# 9xVoice_MikeB_SMD_v101.net
KiCad netlist of a schematic drawn in EAGLE
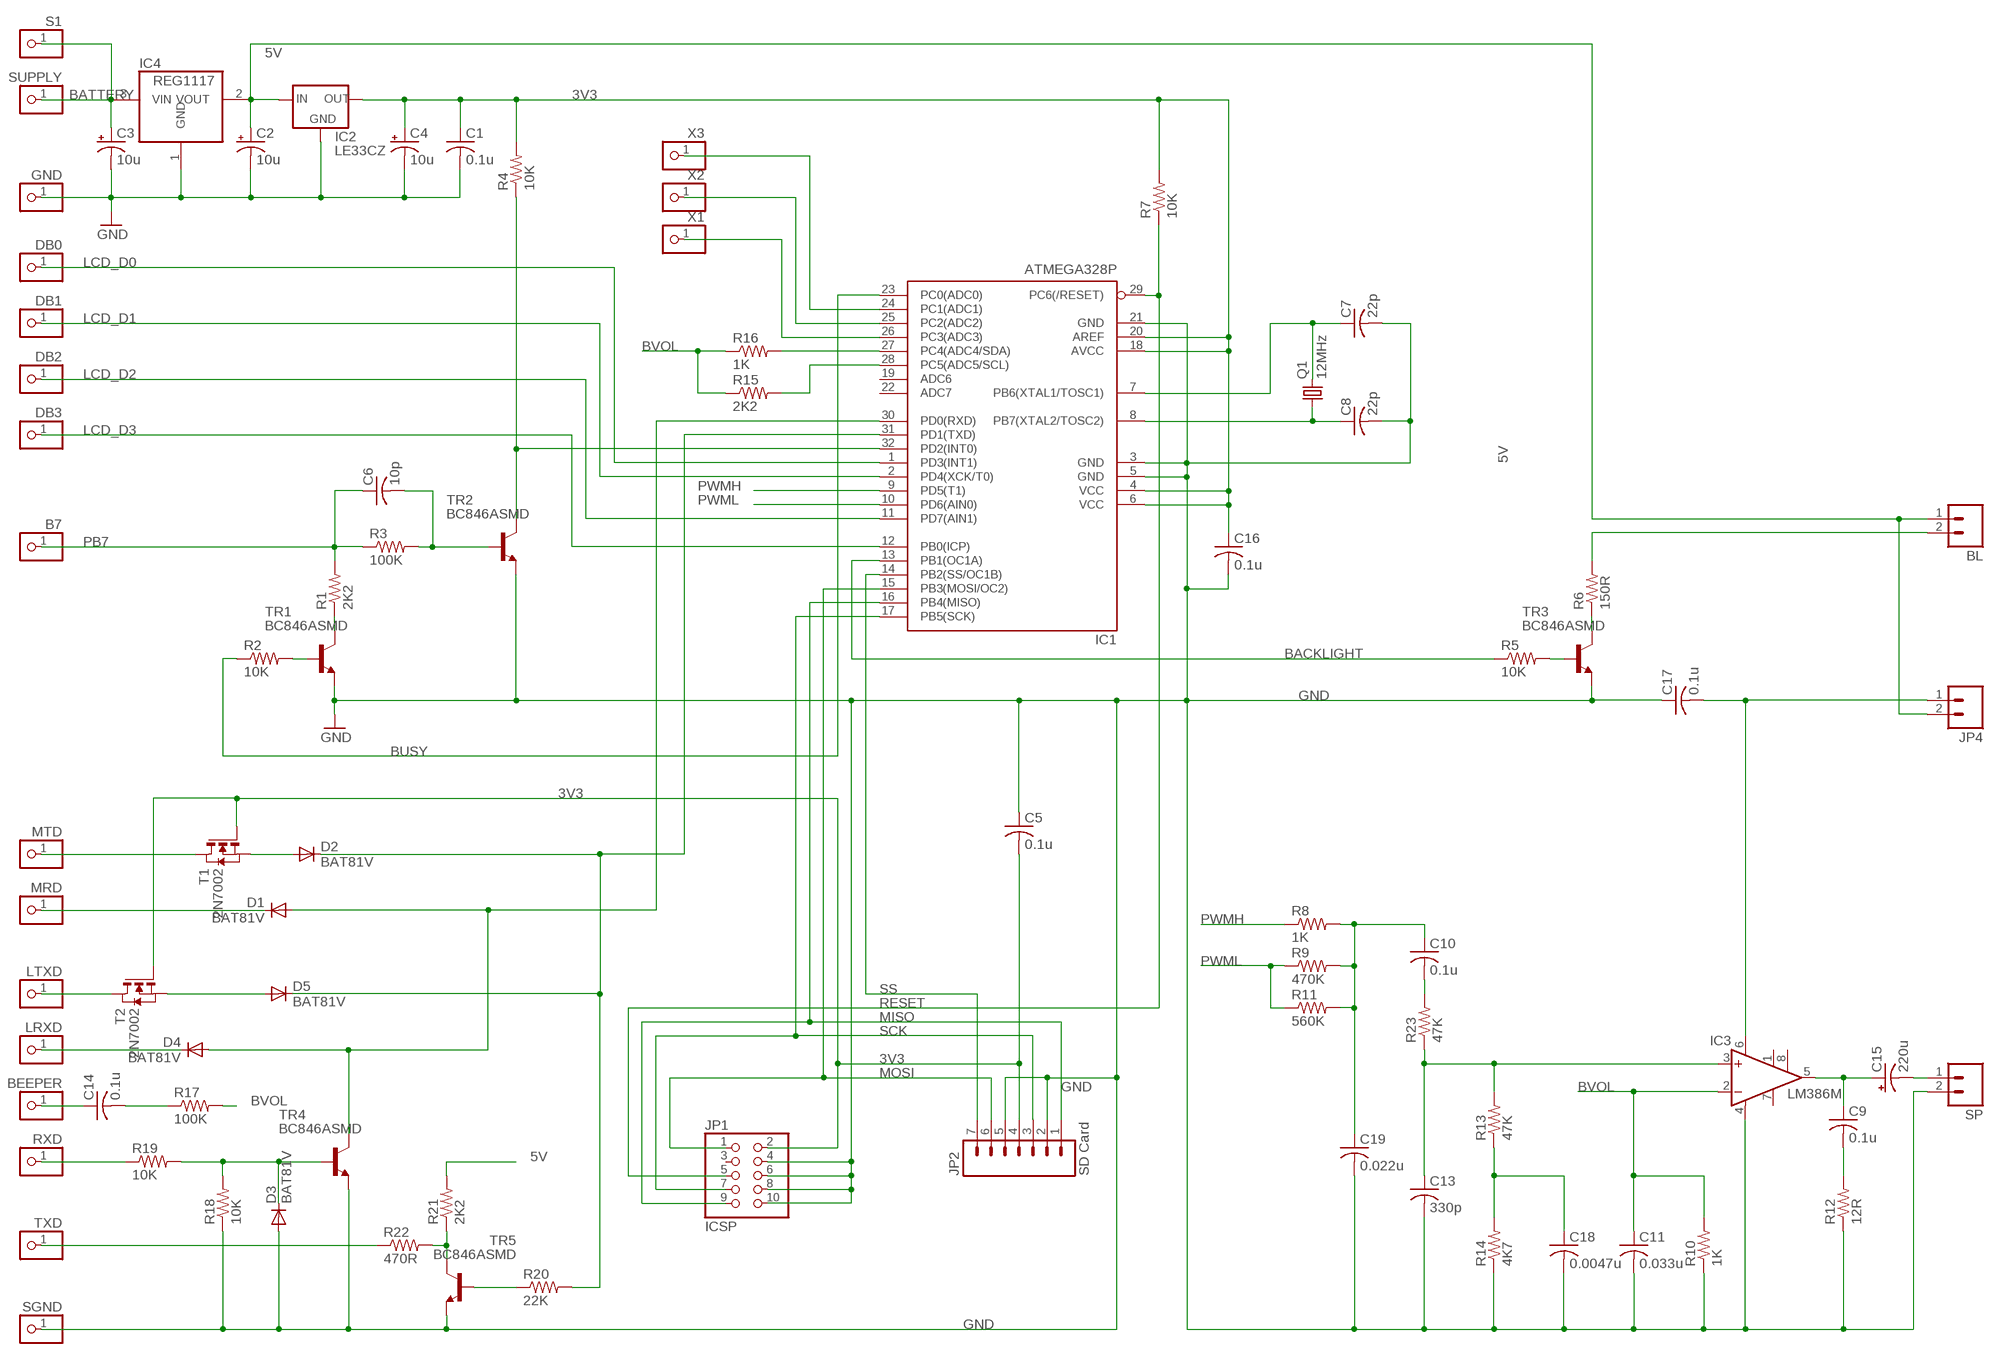
[diagram p0: schematic, sheet 1]

(export (version "E")
  (design (tool "Eeschema 10.0.6"))
  (components
    (comp (ref "B7")
      (value "PINHD-1X1")
      (footprint "eagle-import:1X01")
      (libsource (lib "eagle-import") (part "PINHD-1X1"))
    )
    (comp (ref "BEEPER")
      (value "PINHD-1X1")
      (footprint "eagle-import:1X01")
      (libsource (lib "eagle-import") (part "PINHD-1X1"))
    )
    (comp (ref "BL")
      (value "M02PTH")
      (footprint "eagle-import:1X02")
      (libsource (lib "eagle-import") (part "M02PTH"))
    )
    (comp (ref "C1")
      (value "0.1u")
      (footprint "eagle-import:C1206")
      (libsource (lib "eagle-import") (part "C-USC1206"))
    )
    (comp (ref "C2")
      (value "10u")
      (footprint "eagle-import:A_3216-18R")
      (libsource (lib "eagle-import") (part "CPOL-USA/3216-18R"))
    )
    (comp (ref "C3")
      (value "10u")
      (footprint "eagle-import:A_3216-18R")
      (libsource (lib "eagle-import") (part "CPOL-USA/3216-18R"))
    )
    (comp (ref "C4")
      (value "10u")
      (footprint "eagle-import:A_3216-18R")
      (libsource (lib "eagle-import") (part "CPOL-USA/3216-18R"))
    )
    (comp (ref "C5")
      (value "0.1u")
      (footprint "eagle-import:C1206")
      (libsource (lib "eagle-import") (part "C-USC1206"))
    )
    (comp (ref "C6")
      (value "10p")
      (footprint "eagle-import:C1206")
      (libsource (lib "eagle-import") (part "C-USC1206"))
    )
    (comp (ref "C7")
      (value "22p")
      (footprint "eagle-import:C1206")
      (libsource (lib "eagle-import") (part "C-USC1206"))
    )
    (comp (ref "C8")
      (value "22p")
      (footprint "eagle-import:C1206")
      (libsource (lib "eagle-import") (part "C-USC1206"))
    )
    (comp (ref "C9")
      (value "0.1u")
      (footprint "eagle-import:C1206")
      (libsource (lib "eagle-import") (part "C-USC1206"))
    )
    (comp (ref "C10")
      (value "0.1u")
      (footprint "eagle-import:C1206")
      (libsource (lib "eagle-import") (part "C-USC1206"))
    )
    (comp (ref "C11")
      (value "0.033u")
      (footprint "eagle-import:C1206")
      (libsource (lib "eagle-import") (part "C-USC1206"))
    )
    (comp (ref "C13")
      (value "330p")
      (footprint "eagle-import:C1206")
      (libsource (lib "eagle-import") (part "C-USC1206"))
    )
    (comp (ref "C14")
      (value "0.1u")
      (footprint "eagle-import:C1206")
      (libsource (lib "eagle-import") (part "C-USC1206"))
    )
    (comp (ref "C15")
      (value "220u")
      (footprint "eagle-import:CT7343")
      (libsource (lib "eagle-import") (part "CPOL-USCT7343"))
    )
    (comp (ref "C16")
      (value "0.1u")
      (footprint "eagle-import:C1206")
      (libsource (lib "eagle-import") (part "C-USC1206"))
    )
    (comp (ref "C17")
      (value "0.1u")
      (footprint "eagle-import:C1206")
      (libsource (lib "eagle-import") (part "C-USC1206"))
    )
    (comp (ref "C18")
      (value "0.0047u")
      (footprint "eagle-import:C1206")
      (libsource (lib "eagle-import") (part "C-USC1206"))
    )
    (comp (ref "C19")
      (value "0.022u")
      (footprint "eagle-import:C1206")
      (libsource (lib "eagle-import") (part "C-USC1206"))
    )
    (comp (ref "D1")
      (value "BAT81V")
      (footprint "eagle-import:SOD123")
      (libsource (lib "eagle-import") (part "DIODE-SOD123"))
    )
    (comp (ref "D2")
      (value "BAT81V")
      (footprint "eagle-import:SOD123")
      (libsource (lib "eagle-import") (part "DIODE-SOD123"))
    )
    (comp (ref "D3")
      (value "BAT81V")
      (footprint "eagle-import:SOD123")
      (libsource (lib "eagle-import") (part "DIODE-SOD123"))
    )
    (comp (ref "D4")
      (value "BAT81V")
      (footprint "eagle-import:SOD123")
      (libsource (lib "eagle-import") (part "DIODE-SOD123"))
    )
    (comp (ref "D5")
      (value "BAT81V")
      (footprint "eagle-import:SOD123")
      (libsource (lib "eagle-import") (part "DIODE-SOD123"))
    )
    (comp (ref "DB0")
      (value "PINHD-1X1")
      (footprint "eagle-import:1X01")
      (libsource (lib "eagle-import") (part "PINHD-1X1"))
    )
    (comp (ref "DB1")
      (value "PINHD-1X1")
      (footprint "eagle-import:1X01")
      (libsource (lib "eagle-import") (part "PINHD-1X1"))
    )
    (comp (ref "DB2")
      (value "PINHD-1X1")
      (footprint "eagle-import:1X01")
      (libsource (lib "eagle-import") (part "PINHD-1X1"))
    )
    (comp (ref "DB3")
      (value "PINHD-1X1")
      (footprint "eagle-import:1X01")
      (libsource (lib "eagle-import") (part "PINHD-1X1"))
    )
    (comp (ref "GND")
      (value "PINHD-1X1")
      (footprint "eagle-import:1X01")
      (libsource (lib "eagle-import") (part "PINHD-1X1"))
    )
    (comp (ref "IC1")
      (value "ATMEGA328P")
      (footprint "eagle-import:TQFP32-08")
      (fields
        (field (name "MPN") "ATMEGA8-16AU")
        (field (name "MPN_1") "ATMEGA8-16AU")
        (field (name "OC_FARNELL") "9171371")
        (field (name "OC_NEWARK") "73M8863")
      )
      (libsource (lib "eagle-import") (part "MEGA8-AI"))
    )
    (comp (ref "IC2")
      (value "LE33CZ")
      (footprint "eagle-import:SOT23")
      (libsource (lib "eagle-import") (part "XC63FPM"))
    )
    (comp (ref "IC3")
      (value "LM386M")
      (footprint "eagle-import:SO08")
      (libsource (lib "eagle-import") (part "LM386?-M1"))
    )
    (comp (ref "IC4")
      (value "REG1117")
      (footprint "eagle-import:SOT223")
      (libsource (lib "eagle-import") (part "REG1117"))
    )
    (comp (ref "JP1")
      (value "ICSP")
      (footprint "eagle-import:2X05")
      (libsource (lib "eagle-import") (part "PINHD-2X5"))
    )
    (comp (ref "JP2")
      (value "SD Card")
      (footprint "eagle-import:1X07")
      (libsource (lib "eagle-import") (part "M07"))
    )
    (comp (ref "JP4")
      (value "M02PTH")
      (footprint "eagle-import:1X02")
      (libsource (lib "eagle-import") (part "M02PTH"))
    )
    (comp (ref "LRXD")
      (value "PINHD-1X1")
      (footprint "eagle-import:1X01")
      (libsource (lib "eagle-import") (part "PINHD-1X1"))
    )
    (comp (ref "LTXD")
      (value "PINHD-1X1")
      (footprint "eagle-import:1X01")
      (libsource (lib "eagle-import") (part "PINHD-1X1"))
    )
    (comp (ref "MRD")
      (value "PINHD-1X1")
      (footprint "eagle-import:1X01")
      (libsource (lib "eagle-import") (part "PINHD-1X1"))
    )
    (comp (ref "MTD")
      (value "PINHD-1X1")
      (footprint "eagle-import:1X01")
      (libsource (lib "eagle-import") (part "PINHD-1X1"))
    )
    (comp (ref "Q1")
      (value "12MHz")
      (footprint "eagle-import:2-SMD")
      (libsource (lib "eagle-import") (part "7A"))
    )
    (comp (ref "R1")
      (value "2K2")
      (footprint "eagle-import:R1206")
      (libsource (lib "eagle-import") (part "R-US_R1206"))
    )
    (comp (ref "R2")
      (value "10K")
      (footprint "eagle-import:R1206")
      (libsource (lib "eagle-import") (part "R-US_R1206"))
    )
    (comp (ref "R3")
      (value "100K")
      (footprint "eagle-import:R1206")
      (libsource (lib "eagle-import") (part "R-US_R1206"))
    )
    (comp (ref "R4")
      (value "10K")
      (footprint "eagle-import:R1206")
      (libsource (lib "eagle-import") (part "R-US_R1206"))
    )
    (comp (ref "R5")
      (value "10K")
      (footprint "eagle-import:R1206")
      (libsource (lib "eagle-import") (part "R-US_R1206"))
    )
    (comp (ref "R6")
      (value "150R")
      (footprint "eagle-import:R1206")
      (libsource (lib "eagle-import") (part "R-US_R1206"))
    )
    (comp (ref "R7")
      (value "10K")
      (footprint "eagle-import:R1206")
      (libsource (lib "eagle-import") (part "R-US_R1206"))
    )
    (comp (ref "R8")
      (value "1K")
      (footprint "eagle-import:R1206")
      (libsource (lib "eagle-import") (part "R-US_R1206"))
    )
    (comp (ref "R9")
      (value "470K")
      (footprint "eagle-import:R1206")
      (libsource (lib "eagle-import") (part "R-US_R1206"))
    )
    (comp (ref "R10")
      (value "1K")
      (footprint "eagle-import:R1206")
      (libsource (lib "eagle-import") (part "R-US_R1206"))
    )
    (comp (ref "R11")
      (value "560K")
      (footprint "eagle-import:R1206")
      (libsource (lib "eagle-import") (part "R-US_R1206"))
    )
    (comp (ref "R12")
      (value "12R")
      (footprint "eagle-import:R1206")
      (libsource (lib "eagle-import") (part "R-US_R1206"))
    )
    (comp (ref "R13")
      (value "47K")
      (footprint "eagle-import:R1206")
      (libsource (lib "eagle-import") (part "R-US_R1206"))
    )
    (comp (ref "R14")
      (value "4K7")
      (footprint "eagle-import:R1206")
      (libsource (lib "eagle-import") (part "R-US_R1206"))
    )
    (comp (ref "R15")
      (value "2K2")
      (footprint "eagle-import:R1206")
      (libsource (lib "eagle-import") (part "R-US_R1206"))
    )
    (comp (ref "R16")
      (value "1K")
      (footprint "eagle-import:R1206")
      (libsource (lib "eagle-import") (part "R-US_R1206"))
    )
    (comp (ref "R17")
      (value "100K")
      (footprint "eagle-import:R1206")
      (libsource (lib "eagle-import") (part "R-US_R1206"))
    )
    (comp (ref "R18")
      (value "10K")
      (footprint "eagle-import:R1206")
      (libsource (lib "eagle-import") (part "R-US_R1206"))
    )
    (comp (ref "R19")
      (value "10K")
      (footprint "eagle-import:R1206")
      (libsource (lib "eagle-import") (part "R-US_R1206"))
    )
    (comp (ref "R20")
      (value "22K")
      (footprint "eagle-import:R1206")
      (libsource (lib "eagle-import") (part "R-US_R1206"))
    )
    (comp (ref "R21")
      (value "2K2")
      (footprint "eagle-import:R1206")
      (libsource (lib "eagle-import") (part "R-US_R1206"))
    )
    (comp (ref "R22")
      (value "470R")
      (footprint "eagle-import:R1206")
      (libsource (lib "eagle-import") (part "R-US_R1206"))
    )
    (comp (ref "R23")
      (value "47K")
      (footprint "eagle-import:R1206")
      (libsource (lib "eagle-import") (part "R-US_R1206"))
    )
    (comp (ref "RXD")
      (value "PINHD-1X1")
      (footprint "eagle-import:1X01")
      (libsource (lib "eagle-import") (part "PINHD-1X1"))
    )
    (comp (ref "S1")
      (value "PINHD-1X1")
      (footprint "eagle-import:1X01")
      (libsource (lib "eagle-import") (part "PINHD-1X1"))
    )
    (comp (ref "SGND")
      (value "PINHD-1X1")
      (footprint "eagle-import:1X01")
      (libsource (lib "eagle-import") (part "PINHD-1X1"))
    )
    (comp (ref "SP")
      (value "M02PTH")
      (footprint "eagle-import:1X02")
      (libsource (lib "eagle-import") (part "M02PTH"))
    )
    (comp (ref "SUPPLY")
      (value "PINHD-1X1")
      (footprint "eagle-import:1X01")
      (libsource (lib "eagle-import") (part "PINHD-1X1"))
    )
    (comp (ref "T1")
      (value "2N7002")
      (footprint "eagle-import:SOT-23")
      (libsource (lib "eagle-import") (part "NMOSSOT23"))
    )
    (comp (ref "T2")
      (value "2N7002")
      (footprint "eagle-import:SOT-23")
      (libsource (lib "eagle-import") (part "NMOSSOT23"))
    )
    (comp (ref "TR1")
      (value "BC846ASMD")
      (footprint "eagle-import:SOT23")
      (libsource (lib "eagle-import") (part "BC846SMDA"))
    )
    (comp (ref "TR2")
      (value "BC846ASMD")
      (footprint "eagle-import:SOT23")
      (libsource (lib "eagle-import") (part "BC846SMDA"))
    )
    (comp (ref "TR3")
      (value "BC846ASMD")
      (footprint "eagle-import:SOT23")
      (libsource (lib "eagle-import") (part "BC846SMDA"))
    )
    (comp (ref "TR4")
      (value "BC846ASMD")
      (footprint "eagle-import:SOT23")
      (libsource (lib "eagle-import") (part "BC846SMDA"))
    )
    (comp (ref "TR5")
      (value "BC846ASMD")
      (footprint "eagle-import:SOT23")
      (libsource (lib "eagle-import") (part "BC846SMDA"))
    )
    (comp (ref "TXD")
      (value "PINHD-1X1")
      (footprint "eagle-import:1X01")
      (libsource (lib "eagle-import") (part "PINHD-1X1"))
    )
    (comp (ref "X1")
      (value "PINHD-1X1")
      (footprint "eagle-import:1X01")
      (libsource (lib "eagle-import") (part "PINHD-1X1"))
    )
    (comp (ref "X2")
      (value "PINHD-1X1")
      (footprint "eagle-import:1X01")
      (libsource (lib "eagle-import") (part "PINHD-1X1"))
    )
    (comp (ref "X3")
      (value "PINHD-1X1")
      (footprint "eagle-import:1X01")
      (libsource (lib "eagle-import") (part "PINHD-1X1"))
    )
  )
  (nets
    (net (code "1") (name "/3V3") (class "Default")
      (node (ref "C1") (pin "1") (pinfunction "1_1") (pintype "passive"))
      (node (ref "C16") (pin "1") (pinfunction "1_1") (pintype "passive"))
      (node (ref "C4") (pin "+") (pinfunction "+_+") (pintype "passive"))
      (node (ref "C5") (pin "2") (pinfunction "2_2") (pintype "passive"))
      (node (ref "IC1") (pin "18") (pinfunction "AVCC_18") (pintype "power_in"))
      (node (ref "IC1") (pin "20") (pinfunction "AREF_20") (pintype "passive"))
      (node (ref "IC1") (pin "4") (pinfunction "VCC_4") (pintype "power_in"))
      (node (ref "IC1") (pin "6") (pinfunction "VCC_6") (pintype "power_in"))
      (node (ref "IC2") (pin "2") (pinfunction "OUT_2") (pintype "passive"))
      (node (ref "JP1") (pin "2") (pinfunction "2_2") (pintype "passive"))
      (node (ref "JP2") (pin "4") (pinfunction "4_4") (pintype "passive"))
      (node (ref "R4") (pin "2") (pinfunction "2_2") (pintype "passive"))
      (node (ref "R7") (pin "2") (pinfunction "2_2") (pintype "passive"))
      (node (ref "T1") (pin "3") (pinfunction "G_3") (pintype "passive"))
      (node (ref "T2") (pin "3") (pinfunction "G_3") (pintype "passive"))
    )
    (net (code "2") (name "/5V") (class "Default")
      (node (ref "BL") (pin "1") (pinfunction "1_1") (pintype "passive"))
      (node (ref "C2") (pin "+") (pinfunction "+_+") (pintype "passive"))
      (node (ref "IC2") (pin "3") (pinfunction "IN_3") (pintype "input"))
      (node (ref "IC4") (pin "2") (pinfunction "VOUT_2") (pintype "output"))
      (node (ref "JP4") (pin "2") (pinfunction "2_2") (pintype "passive"))
      (node (ref "R21") (pin "2") (pinfunction "2_2") (pintype "passive"))
    )
    (net (code "3") (name "/BACKLIGHT") (class "Default")
      (node (ref "IC1") (pin "13") (pinfunction "PB1(OC1A)_13") (pintype "bidirectional"))
      (node (ref "R5") (pin "1") (pinfunction "1_1") (pintype "passive"))
    )
    (net (code "4") (name "/BATTERY") (class "Default")
      (node (ref "C3") (pin "+") (pinfunction "+_+") (pintype "passive"))
      (node (ref "IC4") (pin "3") (pinfunction "VIN_3") (pintype "input"))
      (node (ref "S1") (pin "1") (pinfunction "1_1") (pintype "passive"))
      (node (ref "SUPPLY") (pin "1") (pinfunction "1_1") (pintype "passive"))
    )
    (net (code "5") (name "/BUSY") (class "Default")
      (node (ref "IC1") (pin "23") (pinfunction "PC0(ADC0)_23") (pintype "bidirectional"))
      (node (ref "R2") (pin "1") (pinfunction "1_1") (pintype "passive"))
    )
    (net (code "6") (name "/BVOL") (class "Default")
      (node (ref "C11") (pin "1") (pinfunction "1_1") (pintype "passive"))
      (node (ref "IC3") (pin "2") (pinfunction "-IN_2") (pintype "input"))
      (node (ref "R10") (pin "2") (pinfunction "2_2") (pintype "passive"))
      (node (ref "R15") (pin "1") (pinfunction "1_1") (pintype "passive"))
      (node (ref "R16") (pin "1") (pinfunction "1_1") (pintype "passive"))
      (node (ref "R17") (pin "2") (pinfunction "2_2") (pintype "passive"))
    )
    (net (code "7") (name "/LCD_D0") (class "Default")
      (node (ref "DB0") (pin "1") (pinfunction "1_1") (pintype "passive"))
      (node (ref "IC1") (pin "1") (pinfunction "PD3(INT1)_1") (pintype "bidirectional"))
    )
    (net (code "8") (name "/LCD_D1") (class "Default")
      (node (ref "DB1") (pin "1") (pinfunction "1_1") (pintype "passive"))
      (node (ref "IC1") (pin "2") (pinfunction "PD4(XCK/T0)_2") (pintype "bidirectional"))
    )
    (net (code "9") (name "/LCD_D2") (class "Default")
      (node (ref "DB2") (pin "1") (pinfunction "1_1") (pintype "passive"))
      (node (ref "IC1") (pin "11") (pinfunction "PD7(AIN1)_11") (pintype "bidirectional"))
    )
    (net (code "10") (name "/LCD_D3") (class "Default")
      (node (ref "DB3") (pin "1") (pinfunction "1_1") (pintype "passive"))
      (node (ref "IC1") (pin "12") (pinfunction "PB0(ICP)_12") (pintype "bidirectional"))
    )
    (net (code "11") (name "/MISO") (class "Default")
      (node (ref "IC1") (pin "16") (pinfunction "PB4(MISO)_16") (pintype "bidirectional"))
      (node (ref "JP1") (pin "9") (pinfunction "9_9") (pintype "passive"))
      (node (ref "JP2") (pin "1") (pinfunction "1_1") (pintype "passive"))
    )
    (net (code "12") (name "/MOSI") (class "Default")
      (node (ref "IC1") (pin "15") (pinfunction "PB3(MOSI/OC2)_15") (pintype "bidirectional"))
      (node (ref "JP1") (pin "1") (pinfunction "1_1") (pintype "passive"))
      (node (ref "JP2") (pin "6") (pinfunction "6_6") (pintype "passive"))
    )
    (net (code "13") (name "/PB7") (class "Default")
      (node (ref "B7") (pin "1") (pinfunction "1_1") (pintype "passive"))
      (node (ref "C6") (pin "1") (pinfunction "1_1") (pintype "passive"))
      (node (ref "R1") (pin "2") (pinfunction "2_2") (pintype "passive"))
      (node (ref "R3") (pin "1") (pinfunction "1_1") (pintype "passive"))
    )
    (net (code "14") (name "/PWMH") (class "Default")
      (node (ref "IC1") (pin "9") (pinfunction "PD5(T1)_9") (pintype "bidirectional"))
      (node (ref "R8") (pin "1") (pinfunction "1_1") (pintype "passive"))
    )
    (net (code "15") (name "/PWML") (class "Default")
      (node (ref "IC1") (pin "10") (pinfunction "PD6(AIN0)_10") (pintype "bidirectional"))
      (node (ref "R11") (pin "1") (pinfunction "1_1") (pintype "passive"))
      (node (ref "R9") (pin "1") (pinfunction "1_1") (pintype "passive"))
    )
    (net (code "16") (name "/RESET") (class "Default")
      (node (ref "IC1") (pin "29") (pinfunction "PC6(/RESET)_29") (pintype "bidirectional"))
      (node (ref "JP1") (pin "5") (pinfunction "5_5") (pintype "passive"))
      (node (ref "R7") (pin "1") (pinfunction "1_1") (pintype "passive"))
    )
    (net (code "17") (name "/SCK") (class "Default")
      (node (ref "IC1") (pin "17") (pinfunction "PB5(SCK)_17") (pintype "bidirectional"))
      (node (ref "JP1") (pin "7") (pinfunction "7_7") (pintype "passive"))
      (node (ref "JP2") (pin "3") (pinfunction "3_3") (pintype "passive"))
    )
    (net (code "18") (name "/SS") (class "Default")
      (node (ref "IC1") (pin "14") (pinfunction "PB2(SS/OC1B)_14") (pintype "bidirectional"))
      (node (ref "JP2") (pin "7") (pinfunction "7_7") (pintype "passive"))
    )
    (net (code "19") (name "GND") (class "Default")
      (node (ref "C1") (pin "2") (pinfunction "2_2") (pintype "passive"))
      (node (ref "C11") (pin "2") (pinfunction "2_2") (pintype "passive"))
      (node (ref "C13") (pin "2") (pinfunction "2_2") (pintype "passive"))
      (node (ref "C16") (pin "2") (pinfunction "2_2") (pintype "passive"))
      (node (ref "C17") (pin "1") (pinfunction "1_1") (pintype "passive"))
      (node (ref "C18") (pin "2") (pinfunction "2_2") (pintype "passive"))
      (node (ref "C19") (pin "2") (pinfunction "2_2") (pintype "passive"))
      (node (ref "C2") (pin "-") (pinfunction "-_-") (pintype "passive"))
      (node (ref "C3") (pin "-") (pinfunction "-_-") (pintype "passive"))
      (node (ref "C4") (pin "-") (pinfunction "-_-") (pintype "passive"))
      (node (ref "C5") (pin "1") (pinfunction "1_1") (pintype "passive"))
      (node (ref "C7") (pin "2") (pinfunction "2_2") (pintype "passive"))
      (node (ref "C8") (pin "2") (pinfunction "2_2") (pintype "passive"))
      (node (ref "D3") (pin "A") (pinfunction "A_A") (pintype "passive"))
      (node (ref "GND") (pin "1") (pinfunction "1_1") (pintype "passive"))
      (node (ref "IC1") (pin "21") (pinfunction "GND_21") (pintype "power_in"))
      (node (ref "IC1") (pin "3") (pinfunction "GND_3") (pintype "power_in"))
      (node (ref "IC1") (pin "5") (pinfunction "GND_5") (pintype "power_in"))
      (node (ref "IC2") (pin "1") (pinfunction "GND_1") (pintype "input"))
      (node (ref "IC3") (pin "4") (pinfunction "GND_4") (pintype "power_in"))
      (node (ref "IC4") (pin "1") (pinfunction "GND_1") (pintype "power_in"))
      (node (ref "JP1") (pin "10") (pinfunction "10_10") (pintype "passive"))
      (node (ref "JP1") (pin "4") (pinfunction "4_4") (pintype "passive"))
      (node (ref "JP1") (pin "6") (pinfunction "6_6") (pintype "passive"))
      (node (ref "JP1") (pin "8") (pinfunction "8_8") (pintype "passive"))
      (node (ref "JP2") (pin "2") (pinfunction "2_2") (pintype "passive"))
      (node (ref "JP2") (pin "5") (pinfunction "5_5") (pintype "passive"))
      (node (ref "R10") (pin "1") (pinfunction "1_1") (pintype "passive"))
      (node (ref "R12") (pin "1") (pinfunction "1_1") (pintype "passive"))
      (node (ref "R14") (pin "1") (pinfunction "1_1") (pintype "passive"))
      (node (ref "R18") (pin "1") (pinfunction "1_1") (pintype "passive"))
      (node (ref "SGND") (pin "1") (pinfunction "1_1") (pintype "passive"))
      (node (ref "SP") (pin "2") (pinfunction "2_2") (pintype "passive"))
      (node (ref "TR1") (pin "2") (pinfunction "E_2") (pintype "passive"))
      (node (ref "TR2") (pin "2") (pinfunction "E_2") (pintype "passive"))
      (node (ref "TR3") (pin "2") (pinfunction "E_2") (pintype "passive"))
      (node (ref "TR4") (pin "2") (pinfunction "E_2") (pintype "passive"))
      (node (ref "TR5") (pin "2") (pinfunction "E_2") (pintype "passive"))
    )
    (net (code "20") (name "Net-(BEEPER-Pad1)") (class "Default")
      (node (ref "BEEPER") (pin "1") (pinfunction "1_1") (pintype "passive"))
      (node (ref "C14") (pin "1") (pinfunction "1_1") (pintype "passive"))
    )
    (net (code "21") (name "Net-(BL-Pad2)") (class "Default")
      (node (ref "BL") (pin "2") (pinfunction "2_2") (pintype "passive"))
      (node (ref "R6") (pin "2") (pinfunction "2_2") (pintype "passive"))
    )
    (net (code "22") (name "Net-(C9-Pad2)") (class "Default")
      (node (ref "C9") (pin "2") (pinfunction "2_2") (pintype "passive"))
      (node (ref "R12") (pin "2") (pinfunction "2_2") (pintype "passive"))
    )
    (net (code "23") (name "Net-(C10-Pad1)") (class "Default")
      (node (ref "C10") (pin "1") (pinfunction "1_1") (pintype "passive"))
      (node (ref "C19") (pin "1") (pinfunction "1_1") (pintype "passive"))
      (node (ref "R11") (pin "2") (pinfunction "2_2") (pintype "passive"))
      (node (ref "R8") (pin "2") (pinfunction "2_2") (pintype "passive"))
      (node (ref "R9") (pin "2") (pinfunction "2_2") (pintype "passive"))
    )
    (net (code "24") (name "Net-(C10-Pad2)") (class "Default")
      (node (ref "C10") (pin "2") (pinfunction "2_2") (pintype "passive"))
      (node (ref "R23") (pin "2") (pinfunction "2_2") (pintype "passive"))
    )
    (net (code "25") (name "Net-(C14-Pad2)") (class "Default")
      (node (ref "C14") (pin "2") (pinfunction "2_2") (pintype "passive"))
      (node (ref "R17") (pin "1") (pinfunction "1_1") (pintype "passive"))
    )
    (net (code "26") (name "Net-(C15-Pad-)") (class "Default")
      (node (ref "C15") (pin "-") (pinfunction "-_-") (pintype "passive"))
      (node (ref "SP") (pin "1") (pinfunction "1_1") (pintype "passive"))
    )
    (net (code "27") (name "Net-(C18-Pad1)") (class "Default")
      (node (ref "C18") (pin "1") (pinfunction "1_1") (pintype "passive"))
      (node (ref "R13") (pin "1") (pinfunction "1_1") (pintype "passive"))
      (node (ref "R14") (pin "2") (pinfunction "2_2") (pintype "passive"))
    )
    (net (code "28") (name "Net-(D1-PadC)") (class "Default")
      (node (ref "D1") (pin "C") (pinfunction "C_C") (pintype "passive"))
      (node (ref "MRD") (pin "1") (pinfunction "1_1") (pintype "passive"))
    )
    (net (code "29") (name "Net-(D4-PadC)") (class "Default")
      (node (ref "D4") (pin "C") (pinfunction "C_C") (pintype "passive"))
      (node (ref "LRXD") (pin "1") (pinfunction "1_1") (pintype "passive"))
    )
    (net (code "30") (name "Net-(IC1-PB6(XTAL1{slash}TOSC1))") (class "Default")
      (node (ref "C7") (pin "1") (pinfunction "1_1") (pintype "passive"))
      (node (ref "IC1") (pin "7") (pinfunction "PB6(XTAL1/TOSC1)_7") (pintype "bidirectional"))
      (node (ref "Q1") (pin "P$2") (pinfunction "2_P$2") (pintype "passive"))
    )
    (net (code "31") (name "Net-(IC1-PB7(XTAL2{slash}TOSC2))") (class "Default")
      (node (ref "C8") (pin "1") (pinfunction "1_1") (pintype "passive"))
      (node (ref "IC1") (pin "8") (pinfunction "PB7(XTAL2/TOSC2)_8") (pintype "bidirectional"))
      (node (ref "Q1") (pin "P$1") (pinfunction "1_P$1") (pintype "passive"))
    )
    (net (code "32") (name "Net-(IC1-PC1(ADC1))") (class "Default")
      (node (ref "IC1") (pin "24") (pinfunction "PC1(ADC1)_24") (pintype "bidirectional"))
      (node (ref "X3") (pin "1") (pinfunction "1_1") (pintype "passive"))
    )
    (net (code "33") (name "Net-(IC1-PC2(ADC2))") (class "Default")
      (node (ref "IC1") (pin "25") (pinfunction "PC2(ADC2)_25") (pintype "bidirectional"))
      (node (ref "X2") (pin "1") (pinfunction "1_1") (pintype "passive"))
    )
    (net (code "34") (name "Net-(IC1-PC3(ADC3))") (class "Default")
      (node (ref "IC1") (pin "26") (pinfunction "PC3(ADC3)_26") (pintype "bidirectional"))
      (node (ref "X1") (pin "1") (pinfunction "1_1") (pintype "passive"))
    )
    (net (code "35") (name "Net-(IC1-PC4(ADC4{slash}SDA))") (class "Default")
      (node (ref "IC1") (pin "27") (pinfunction "PC4(ADC4/SDA)_27") (pintype "bidirectional"))
      (node (ref "R16") (pin "2") (pinfunction "2_2") (pintype "passive"))
    )
    (net (code "36") (name "Net-(IC1-PC5(ADC5{slash}SCL))") (class "Default")
      (node (ref "IC1") (pin "28") (pinfunction "PC5(ADC5/SCL)_28") (pintype "bidirectional"))
      (node (ref "R15") (pin "2") (pinfunction "2_2") (pintype "passive"))
    )
    (net (code "37") (name "Net-(IC1-PD0(RXD))") (class "Default")
      (node (ref "D1") (pin "A") (pinfunction "A_A") (pintype "passive"))
      (node (ref "D4") (pin "A") (pinfunction "A_A") (pintype "passive"))
      (node (ref "IC1") (pin "30") (pinfunction "PD0(RXD)_30") (pintype "bidirectional"))
      (node (ref "TR4") (pin "3") (pinfunction "C_3") (pintype "passive"))
    )
    (net (code "38") (name "Net-(IC1-PD1(TXD))") (class "Default")
      (node (ref "D2") (pin "C") (pinfunction "C_C") (pintype "passive"))
      (node (ref "D5") (pin "C") (pinfunction "C_C") (pintype "passive"))
      (node (ref "IC1") (pin "31") (pinfunction "PD1(TXD)_31") (pintype "bidirectional"))
      (node (ref "R20") (pin "2") (pinfunction "2_2") (pintype "passive"))
    )
    (net (code "39") (name "Net-(IC1-PD2(INT0))") (class "Default")
      (node (ref "IC1") (pin "32") (pinfunction "PD2(INT0)_32") (pintype "bidirectional"))
      (node (ref "R4") (pin "1") (pinfunction "1_1") (pintype "passive"))
      (node (ref "TR2") (pin "3") (pinfunction "C_3") (pintype "passive"))
    )
    (net (code "40") (name "Net-(IC3-+IN)") (class "Default")
      (node (ref "C13") (pin "1") (pinfunction "1_1") (pintype "passive"))
      (node (ref "IC3") (pin "3") (pinfunction "+IN_3") (pintype "input"))
      (node (ref "R13") (pin "2") (pinfunction "2_2") (pintype "passive"))
      (node (ref "R23") (pin "1") (pinfunction "1_1") (pintype "passive"))
    )
    (net (code "41") (name "Net-(IC3-OUT)") (class "Default")
      (node (ref "C15") (pin "+") (pinfunction "+_+") (pintype "passive"))
      (node (ref "C9") (pin "1") (pinfunction "1_1") (pintype "passive"))
      (node (ref "IC3") (pin "5") (pinfunction "OUT_5") (pintype "output"))
    )
    (net (code "42") (name "Net-(IC3-VS)") (class "Default")
      (node (ref "C17") (pin "2") (pinfunction "2_2") (pintype "passive"))
      (node (ref "IC3") (pin "6") (pinfunction "VS_6") (pintype "power_in"))
      (node (ref "JP4") (pin "1") (pinfunction "1_1") (pintype "passive"))
    )
    (net (code "43") (name "Net-(R19-Pad1)") (class "Default")
      (node (ref "R19") (pin "1") (pinfunction "1_1") (pintype "passive"))
      (node (ref "RXD") (pin "1") (pinfunction "1_1") (pintype "passive"))
    )
    (net (code "44") (name "Net-(R22-Pad1)") (class "Default")
      (node (ref "R22") (pin "1") (pinfunction "1_1") (pintype "passive"))
      (node (ref "TXD") (pin "1") (pinfunction "1_1") (pintype "passive"))
    )
    (net (code "45") (name "Net-(T1-D)") (class "Default")
      (node (ref "MTD") (pin "1") (pinfunction "1_1") (pintype "passive"))
      (node (ref "T1") (pin "1") (pinfunction "D_1") (pintype "passive"))
    )
    (net (code "46") (name "Net-(T1-S)") (class "Default")
      (node (ref "D2") (pin "A") (pinfunction "A_A") (pintype "passive"))
      (node (ref "T1") (pin "2") (pinfunction "S_2") (pintype "passive"))
    )
    (net (code "47") (name "Net-(T2-D)") (class "Default")
      (node (ref "LTXD") (pin "1") (pinfunction "1_1") (pintype "passive"))
      (node (ref "T2") (pin "1") (pinfunction "D_1") (pintype "passive"))
    )
    (net (code "48") (name "Net-(T2-S)") (class "Default")
      (node (ref "D5") (pin "A") (pinfunction "A_A") (pintype "passive"))
      (node (ref "T2") (pin "2") (pinfunction "S_2") (pintype "passive"))
    )
    (net (code "49") (name "Net-(TR1-B)") (class "Default")
      (node (ref "R2") (pin "2") (pinfunction "2_2") (pintype "passive"))
      (node (ref "TR1") (pin "1") (pinfunction "B_1") (pintype "passive"))
    )
    (net (code "50") (name "Net-(TR1-C)") (class "Default")
      (node (ref "R1") (pin "1") (pinfunction "1_1") (pintype "passive"))
      (node (ref "TR1") (pin "3") (pinfunction "C_3") (pintype "passive"))
    )
    (net (code "51") (name "Net-(TR2-B)") (class "Default")
      (node (ref "C6") (pin "2") (pinfunction "2_2") (pintype "passive"))
      (node (ref "R3") (pin "2") (pinfunction "2_2") (pintype "passive"))
      (node (ref "TR2") (pin "1") (pinfunction "B_1") (pintype "passive"))
    )
    (net (code "52") (name "Net-(TR3-B)") (class "Default")
      (node (ref "R5") (pin "2") (pinfunction "2_2") (pintype "passive"))
      (node (ref "TR3") (pin "1") (pinfunction "B_1") (pintype "passive"))
    )
    (net (code "53") (name "Net-(TR3-C)") (class "Default")
      (node (ref "R6") (pin "1") (pinfunction "1_1") (pintype "passive"))
      (node (ref "TR3") (pin "3") (pinfunction "C_3") (pintype "passive"))
    )
    (net (code "54") (name "Net-(TR4-B)") (class "Default")
      (node (ref "D3") (pin "C") (pinfunction "C_C") (pintype "passive"))
      (node (ref "R18") (pin "2") (pinfunction "2_2") (pintype "passive"))
      (node (ref "R19") (pin "2") (pinfunction "2_2") (pintype "passive"))
      (node (ref "TR4") (pin "1") (pinfunction "B_1") (pintype "passive"))
    )
    (net (code "55") (name "Net-(TR5-B)") (class "Default")
      (node (ref "R20") (pin "1") (pinfunction "1_1") (pintype "passive"))
      (node (ref "TR5") (pin "1") (pinfunction "B_1") (pintype "passive"))
    )
    (net (code "56") (name "Net-(TR5-C)") (class "Default")
      (node (ref "R21") (pin "1") (pinfunction "1_1") (pintype "passive"))
      (node (ref "R22") (pin "2") (pinfunction "2_2") (pintype "passive"))
      (node (ref "TR5") (pin "3") (pinfunction "C_3") (pintype "passive"))
    )
    (net (code "57") (name "unconnected-(IC1-ADC6-Pad19)") (class "Default")
      (node (ref "IC1") (pin "19") (pinfunction "ADC6_19") (pintype "bidirectional"))
    )
    (net (code "58") (name "unconnected-(IC1-ADC7-Pad22)") (class "Default")
      (node (ref "IC1") (pin "22") (pinfunction "ADC7_22") (pintype "bidirectional"))
    )
    (net (code "59") (name "unconnected-(IC3-BYPASS-Pad7)") (class "Default")
      (node (ref "IC3") (pin "7") (pinfunction "BYPASS_7") (pintype "passive"))
    )
    (net (code "60") (name "unconnected-(IC3-GAIN-Pad1)") (class "Default")
      (node (ref "IC3") (pin "1") (pinfunction "GAIN_1") (pintype "passive"))
    )
    (net (code "61") (name "unconnected-(IC3-GAIN-Pad8)") (class "Default")
      (node (ref "IC3") (pin "8") (pinfunction "GAIN_8") (pintype "passive"))
    )
    (net (code "62") (name "unconnected-(JP1-Pad3)") (class "Default")
      (node (ref "JP1") (pin "3") (pinfunction "3_3") (pintype "passive"))
    )
  )
)
